# EasyEDA_Schematic_V3_0.net
KiCad netlist of a schematic drawn in EasyEDA
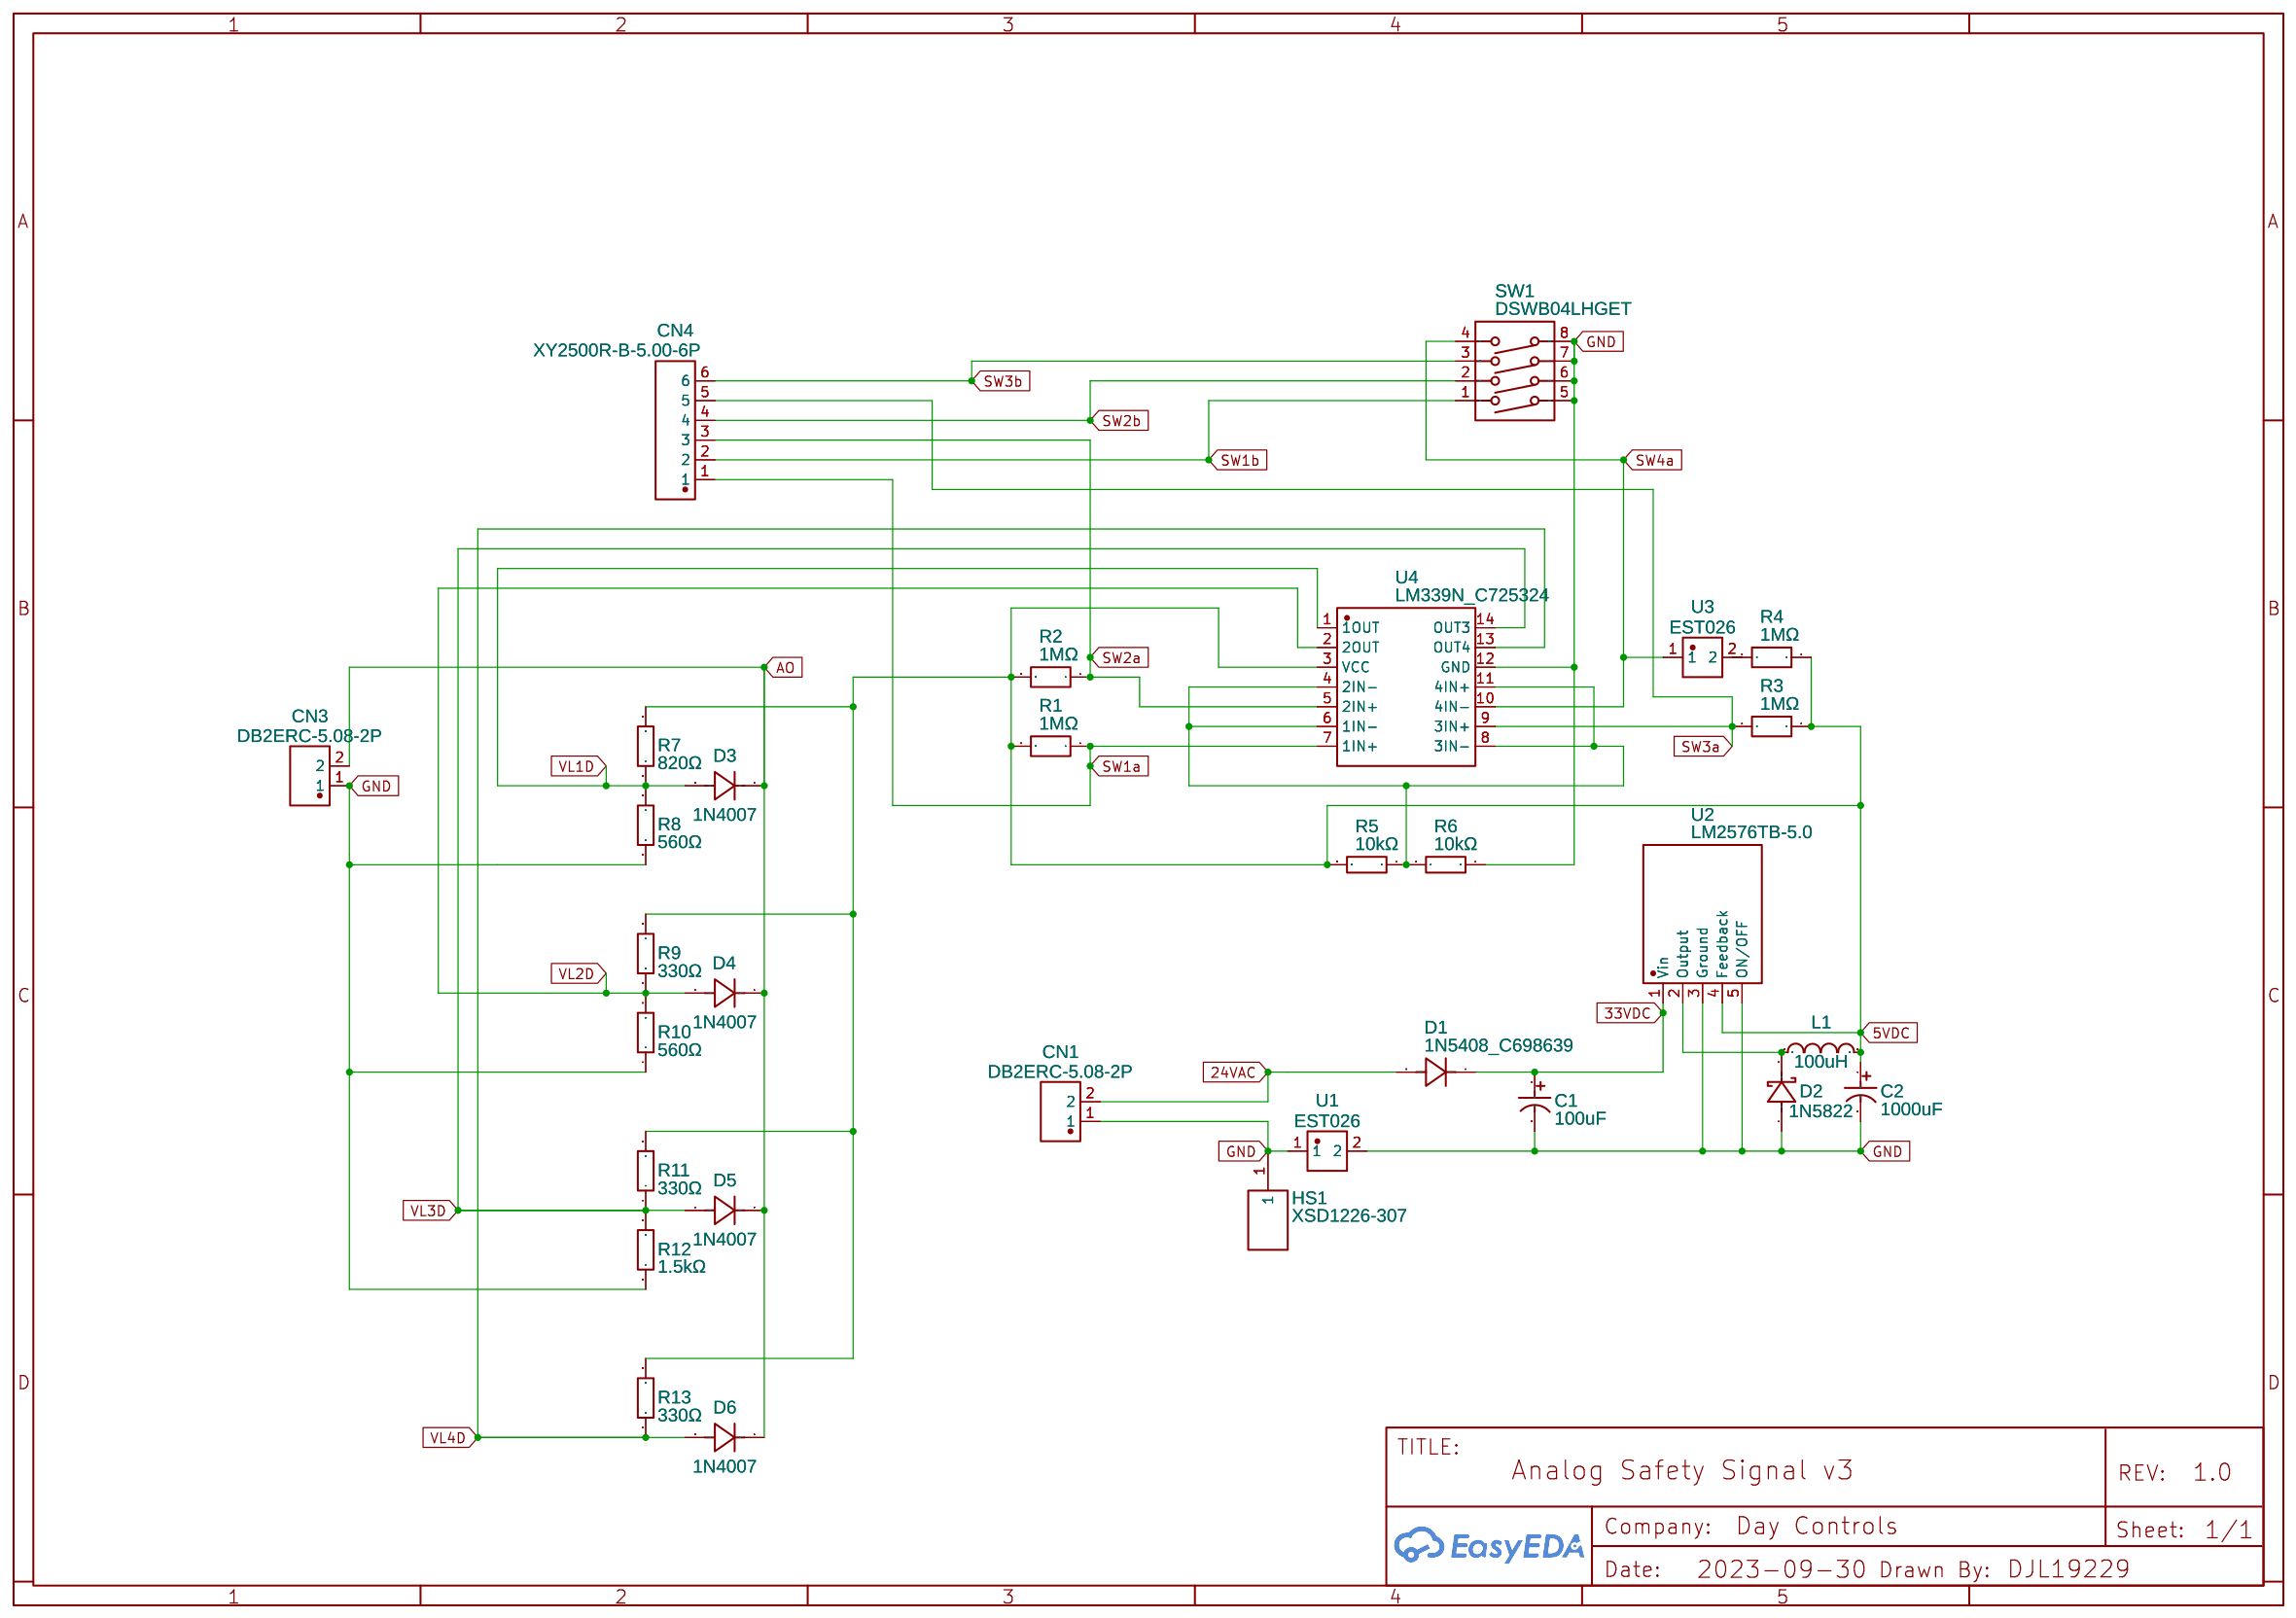
[diagram p0: schematic sheet]

(export (version "E")
  (design (tool "Eeschema 10.0.6"))
  (components
    (comp (ref "C1")
      (value "100uF")
      (fields
        (field (name "Manufacturer Part") "GR107M050F12RR0VH4FP0")
        (field (name "Manufacturer") "CX(承兴)")
      )
      (libsource (lib "") (part "100uF 50V 8*12Black high frequency"))
    )
    (comp (ref "C2")
      (value "1000uF")
      (fields
        (field (name "Manufacturer Part") "35YXJ1000M12.5X20")
        (field (name "Manufacturer") "rubycon(红宝石)")
      )
      (libsource (lib "") (part "35YXJ1000M12.5X20"))
    )
    (comp (ref "CN1")
      (value "DB2ERC-5.08-2P")
      (fields
        (field (name "Manufacturer Part") "DB2ERC-5.08-2P-GN")
        (field (name "Manufacturer") "DIBO(地博电气)")
      )
      (libsource (lib "") (part "DB2ERC-5.08-2P"))
    )
    (comp (ref "CN3")
      (value "DB2ERC-5.08-2P")
      (fields
        (field (name "Manufacturer Part") "DB2ERC-5.08-2P-GN")
        (field (name "Manufacturer") "DIBO(地博电气)")
      )
      (libsource (lib "") (part "DB2ERC-5.08-2P"))
    )
    (comp (ref "CN4")
      (value "XY2500R-B-5.00-6P")
      (fields (field (name "Manufacturer") "XINLAIYA(新莱亚)"))
      (libsource (lib "") (part "XY2500R-B-5.00-6P"))
    )
    (comp (ref "D1")
      (value "1N5408_C698639")
      (fields (field (name "Manufacturer Part") "1N5408") (field (name "Manufacturer") "YANGJIE(扬杰)"))
      (libsource (lib "") (part "1N5408_C698639"))
    )
    (comp (ref "D2")
      (value "1N5822")
      (fields (field (name "Manufacturer") "FUXINSEMI(富芯森美)"))
      (libsource (lib "") (part "1N5822_C3018526"))
    )
    (comp (ref "D3")
      (value "1N4007")
      (fields (field (name "Manufacturer") "YANGJIE(扬杰)"))
      (libsource (lib "") (part "1N4007_C2986225"))
    )
    (comp (ref "D4")
      (value "1N4007")
      (fields (field (name "Manufacturer") "YANGJIE(扬杰)"))
      (libsource (lib "") (part "1N4007_C2986225"))
    )
    (comp (ref "D5")
      (value "1N4007")
      (fields (field (name "Manufacturer") "YANGJIE(扬杰)"))
      (libsource (lib "") (part "1N4007_C2986225"))
    )
    (comp (ref "D6")
      (value "1N4007")
      (fields (field (name "Manufacturer") "YANGJIE(扬杰)"))
      (libsource (lib "") (part "1N4007_C2986225"))
    )
    (comp (ref "HS1")
      (value "XSD1226-307")
      (fields (field (name "Manufacturer") "XSD(鑫顺达)"))
      (libsource (lib "") (part "XSD1226-307"))
    )
    (comp (ref "L1")
      (value "100uH")
      (fields (field (name "Manufacturer Part") "VLU0810-101K") (field (name "Manufacturer") "FH(风华)"))
      (libsource (lib "") (part "VLU0810-101K"))
    )
    (comp (ref "R1")
      (value "1MΩ")
      (fields
        (field (name "Manufacturer Part") "MF1/4W-1MΩ±1%T52")
        (field (name "Manufacturer") "Huaxing Mechanical-Elec.")
      )
      (libsource (lib "") (part "MF1/4W-1MΩ±1%T52"))
    )
    (comp (ref "R2")
      (value "1MΩ")
      (fields
        (field (name "Manufacturer Part") "MF1/4W-1MΩ±1%T52")
        (field (name "Manufacturer") "Huaxing Mechanical-Elec.")
      )
      (libsource (lib "") (part "MF1/4W-1MΩ±1%T52"))
    )
    (comp (ref "R3")
      (value "1MΩ")
      (fields
        (field (name "Manufacturer Part") "MF1/4W-1MΩ±1%T52")
        (field (name "Manufacturer") "Huaxing Mechanical-Elec.")
      )
      (libsource (lib "") (part "MF1/4W-1MΩ±1%T52"))
    )
    (comp (ref "R4")
      (value "1MΩ")
      (fields
        (field (name "Manufacturer Part") "MF1/4W-1MΩ±1%T52")
        (field (name "Manufacturer") "Huaxing Mechanical-Elec.")
      )
      (libsource (lib "") (part "MF1/4W-1MΩ±1%T52"))
    )
    (comp (ref "R5")
      (value "10kΩ")
      (fields (field (name "Manufacturer Part") "MF1/4W-10KΩ±1% T") (field (name "Manufacturer") "CCO(千志电子)"))
      (libsource (lib "") (part "MF1/4W-10KΩ±1% T52"))
    )
    (comp (ref "R6")
      (value "10kΩ")
      (fields (field (name "Manufacturer Part") "MF1/4W-10KΩ±1% T") (field (name "Manufacturer") "CCO(千志电子)"))
      (libsource (lib "") (part "MF1/4W-10KΩ±1% T52"))
    )
    (comp (ref "R7")
      (value "820Ω")
      (fields
        (field (name "Manufacturer Part") "MF1/4W ±1% 820Ω STB5")
        (field (name "Manufacturer") "VO(翔胜)")
      )
      (libsource (lib "") (part "MF1/4W ±1% 820Ω STB5"))
    )
    (comp (ref "R8")
      (value "560Ω")
      (fields (field (name "Manufacturer Part") "MFR-25FTE52-560R") (field (name "Manufacturer") "YAGEO(国巨)"))
      (libsource (lib "") (part "MFR-25FTE52-560R"))
    )
    (comp (ref "R9")
      (value "330Ω")
      (fields (field (name "Manufacturer Part") "MFR-25JT-52-330R") (field (name "Manufacturer") "YAGEO(国巨)"))
      (libsource (lib "") (part "MFR-25JT-52-330R"))
    )
    (comp (ref "R10")
      (value "560Ω")
      (fields (field (name "Manufacturer Part") "MFR-25FTE52-560R") (field (name "Manufacturer") "YAGEO(国巨)"))
      (libsource (lib "") (part "MFR-25FTE52-560R"))
    )
    (comp (ref "R11")
      (value "330Ω")
      (fields (field (name "Manufacturer Part") "MFR-25JT-52-330R") (field (name "Manufacturer") "YAGEO(国巨)"))
      (libsource (lib "") (part "MFR-25JT-52-330R"))
    )
    (comp (ref "R12")
      (value "1.5kΩ")
      (fields
        (field (name "Manufacturer Part") "MF1/4W-1.5KΩ±1% T")
        (field (name "Manufacturer") "CCO(千志电子)")
      )
      (libsource (lib "") (part "MF1/4W-1.5KΩ±1% T52"))
    )
    (comp (ref "R13")
      (value "330Ω")
      (fields (field (name "Manufacturer Part") "MFR-25JT-52-330R") (field (name "Manufacturer") "YAGEO(国巨)"))
      (libsource (lib "") (part "MFR-25JT-52-330R"))
    )
    (comp (ref "SW1")
      (value "DSWB04LHGET")
      (fields (field (name "Manufacturer Part") "拨码开关,平拨开关,DSWB04LHGET") (field (name "Manufacturer") "YE"))
      (libsource (lib "") (part "DSWB04LHGET"))
    )
    (comp (ref "U1")
      (value "EST026")
      (fields (field (name "Manufacturer") "xcfuse(旭程)"))
      (libsource (lib "") (part "EST026"))
    )
    (comp (ref "U2")
      (value "LM2576TB-5.0")
      (fields (field (name "Manufacturer") "HGSEMI(华冠)"))
      (libsource (lib "") (part "LM2576TB-5.0"))
    )
    (comp (ref "U3")
      (value "EST026")
      (fields (field (name "Manufacturer") "xcfuse(旭程)"))
      (libsource (lib "") (part "EST026"))
    )
    (comp (ref "U4")
      (value "LM339N_C725324")
      (fields (field (name "Manufacturer Part") "LM339N") (field (name "Manufacturer") "HGSEMI"))
      (libsource (lib "") (part "LM339N_C725324"))
    )
  )
  (nets
    (net (code "1") (name "5VDC") (class "Default")
      (node (ref "C2") (pin "1") (pinfunction "1_1") (pintype "input"))
      (node (ref "L1") (pin "2") (pinfunction "2_2") (pintype "unspecified"))
      (node (ref "R1") (pin "2") (pinfunction "2_2") (pintype "unspecified"))
      (node (ref "R11") (pin "2") (pinfunction "2_2") (pintype "unspecified"))
      (node (ref "R13") (pin "2") (pinfunction "2_2") (pintype "unspecified"))
      (node (ref "R2") (pin "2") (pinfunction "2_2") (pintype "unspecified"))
      (node (ref "R3") (pin "1") (pinfunction "1_1") (pintype "unspecified"))
      (node (ref "R4") (pin "1") (pinfunction "1_1") (pintype "unspecified"))
      (node (ref "R5") (pin "2") (pinfunction "2_2") (pintype "unspecified"))
      (node (ref "R7") (pin "2") (pinfunction "2_2") (pintype "input"))
      (node (ref "R9") (pin "2") (pinfunction "2_2") (pintype "unspecified"))
      (node (ref "U2") (pin "4") (pinfunction "Feedback_4") (pintype "unspecified"))
      (node (ref "U4") (pin "3") (pinfunction "VCC_3") (pintype "unspecified"))
    )
    (net (code "2") (name "24VAC") (class "Default")
      (node (ref "CN1") (pin "2") (pinfunction "2_2") (pintype "unspecified"))
      (node (ref "D1") (pin "2") (pinfunction "A_2") (pintype "unspecified"))
    )
    (net (code "3") (name "33VDC") (class "Default")
      (node (ref "C1") (pin "1") (pinfunction "1_1") (pintype "input"))
      (node (ref "D1") (pin "1") (pinfunction "K_1") (pintype "unspecified"))
      (node (ref "U2") (pin "1") (pinfunction "Vin_1") (pintype "unspecified"))
    )
    (net (code "4") (name "AO") (class "Default")
      (node (ref "CN3") (pin "2") (pinfunction "2_2") (pintype "unspecified"))
      (node (ref "D3") (pin "1") (pinfunction "K_1") (pintype "unspecified"))
      (node (ref "D4") (pin "1") (pinfunction "K_1") (pintype "unspecified"))
      (node (ref "D5") (pin "1") (pinfunction "K_1") (pintype "unspecified"))
      (node (ref "D6") (pin "1") (pinfunction "K_1") (pintype "unspecified"))
    )
    (net (code "5") (name "GND") (class "Default")
      (node (ref "C1") (pin "2") (pinfunction "2_2") (pintype "input"))
      (node (ref "C2") (pin "2") (pinfunction "2_2") (pintype "input"))
      (node (ref "CN1") (pin "1") (pinfunction "1_1") (pintype "unspecified"))
      (node (ref "CN3") (pin "1") (pinfunction "1_1") (pintype "unspecified"))
      (node (ref "D2") (pin "1") (pinfunction "A_1") (pintype "unspecified"))
      (node (ref "HS1") (pin "1") (pinfunction "1_1") (pintype "unspecified"))
      (node (ref "R10") (pin "1") (pinfunction "1_1") (pintype "unspecified"))
      (node (ref "R12") (pin "1") (pinfunction "1_1") (pintype "unspecified"))
      (node (ref "R6") (pin "1") (pinfunction "1_1") (pintype "unspecified"))
      (node (ref "R8") (pin "1") (pinfunction "1_1") (pintype "unspecified"))
      (node (ref "SW1") (pin "5") (pinfunction "5_5") (pintype "unspecified"))
      (node (ref "SW1") (pin "6") (pinfunction "6_6") (pintype "unspecified"))
      (node (ref "SW1") (pin "7") (pinfunction "7_7") (pintype "unspecified"))
      (node (ref "SW1") (pin "8") (pinfunction "8_8") (pintype "unspecified"))
      (node (ref "U1") (pin "1") (pinfunction "1_1") (pintype "unspecified"))
      (node (ref "U1") (pin "2") (pinfunction "2_2") (pintype "unspecified"))
      (node (ref "U2") (pin "3") (pinfunction "Ground_3") (pintype "unspecified"))
      (node (ref "U2") (pin "5") (pinfunction "ON/OFF_5") (pintype "unspecified"))
      (node (ref "U4") (pin "12") (pinfunction "GND_12") (pintype "unspecified"))
    )
    (net (code "6") (name "Net-(D2-K)") (class "Default")
      (node (ref "D2") (pin "2") (pinfunction "K_2") (pintype "unspecified"))
      (node (ref "L1") (pin "1") (pinfunction "1_1") (pintype "unspecified"))
      (node (ref "U2") (pin "2") (pinfunction "Output_2") (pintype "unspecified"))
    )
    (net (code "7") (name "Net-(R4-Pad2)") (class "Default")
      (node (ref "R4") (pin "2") (pinfunction "2_2") (pintype "unspecified"))
      (node (ref "U3") (pin "2") (pinfunction "2_2") (pintype "unspecified"))
    )
    (net (code "8") (name "Net-(U4-1IN-)") (class "Default")
      (node (ref "R5") (pin "1") (pinfunction "1_1") (pintype "unspecified"))
      (node (ref "R6") (pin "2") (pinfunction "2_2") (pintype "unspecified"))
      (node (ref "U4") (pin "11") (pinfunction "4IN+_11") (pintype "unspecified"))
      (node (ref "U4") (pin "4") (pinfunction "2IN-_4") (pintype "unspecified"))
      (node (ref "U4") (pin "6") (pinfunction "1IN-_6") (pintype "unspecified"))
      (node (ref "U4") (pin "8") (pinfunction "3IN-_8") (pintype "unspecified"))
    )
    (net (code "9") (name "SW1a") (class "Default")
      (node (ref "CN4") (pin "1") (pinfunction "1_1") (pintype "unspecified"))
      (node (ref "R1") (pin "1") (pinfunction "1_1") (pintype "unspecified"))
      (node (ref "U4") (pin "7") (pinfunction "1IN+_7") (pintype "unspecified"))
    )
    (net (code "10") (name "SW1b") (class "Default")
      (node (ref "CN4") (pin "2") (pinfunction "2_2") (pintype "unspecified"))
      (node (ref "SW1") (pin "1") (pinfunction "1_1") (pintype "unspecified"))
    )
    (net (code "11") (name "SW2a") (class "Default")
      (node (ref "CN4") (pin "3") (pinfunction "3_3") (pintype "unspecified"))
      (node (ref "R2") (pin "1") (pinfunction "1_1") (pintype "unspecified"))
      (node (ref "U4") (pin "5") (pinfunction "2IN+_5") (pintype "unspecified"))
    )
    (net (code "12") (name "SW2b") (class "Default")
      (node (ref "CN4") (pin "4") (pinfunction "4_4") (pintype "unspecified"))
      (node (ref "SW1") (pin "2") (pinfunction "2_2") (pintype "unspecified"))
    )
    (net (code "13") (name "SW3a") (class "Default")
      (node (ref "CN4") (pin "5") (pinfunction "5_5") (pintype "unspecified"))
      (node (ref "R3") (pin "2") (pinfunction "2_2") (pintype "unspecified"))
      (node (ref "U4") (pin "9") (pinfunction "3IN+_9") (pintype "unspecified"))
    )
    (net (code "14") (name "SW3b") (class "Default")
      (node (ref "CN4") (pin "6") (pinfunction "6_6") (pintype "unspecified"))
      (node (ref "SW1") (pin "3") (pinfunction "3_3") (pintype "unspecified"))
    )
    (net (code "15") (name "SW4a") (class "Default")
      (node (ref "SW1") (pin "4") (pinfunction "4_4") (pintype "unspecified"))
      (node (ref "U3") (pin "1") (pinfunction "1_1") (pintype "unspecified"))
      (node (ref "U4") (pin "10") (pinfunction "4IN-_10") (pintype "unspecified"))
    )
    (net (code "16") (name "VL1D") (class "Default")
      (node (ref "D3") (pin "2") (pinfunction "A_2") (pintype "unspecified"))
      (node (ref "R7") (pin "1") (pinfunction "1_1") (pintype "input"))
      (node (ref "R8") (pin "2") (pinfunction "2_2") (pintype "unspecified"))
      (node (ref "U4") (pin "1") (pinfunction "1OUT_1") (pintype "unspecified"))
    )
    (net (code "17") (name "VL2D") (class "Default")
      (node (ref "D4") (pin "2") (pinfunction "A_2") (pintype "unspecified"))
      (node (ref "R10") (pin "2") (pinfunction "2_2") (pintype "unspecified"))
      (node (ref "R9") (pin "1") (pinfunction "1_1") (pintype "unspecified"))
      (node (ref "U4") (pin "2") (pinfunction "2OUT_2") (pintype "unspecified"))
    )
    (net (code "18") (name "VL3D") (class "Default")
      (node (ref "D5") (pin "2") (pinfunction "A_2") (pintype "unspecified"))
      (node (ref "R11") (pin "1") (pinfunction "1_1") (pintype "unspecified"))
      (node (ref "R12") (pin "2") (pinfunction "2_2") (pintype "unspecified"))
      (node (ref "U4") (pin "14") (pinfunction "OUT3_14") (pintype "unspecified"))
    )
    (net (code "19") (name "VL4D") (class "Default")
      (node (ref "D6") (pin "2") (pinfunction "A_2") (pintype "unspecified"))
      (node (ref "R13") (pin "1") (pinfunction "1_1") (pintype "unspecified"))
      (node (ref "U4") (pin "13") (pinfunction "OUT4_13") (pintype "unspecified"))
    )
  )
)
